# STM32_3_Sheet3.net
KiCad netlist of a schematic drawn in Altium Designer
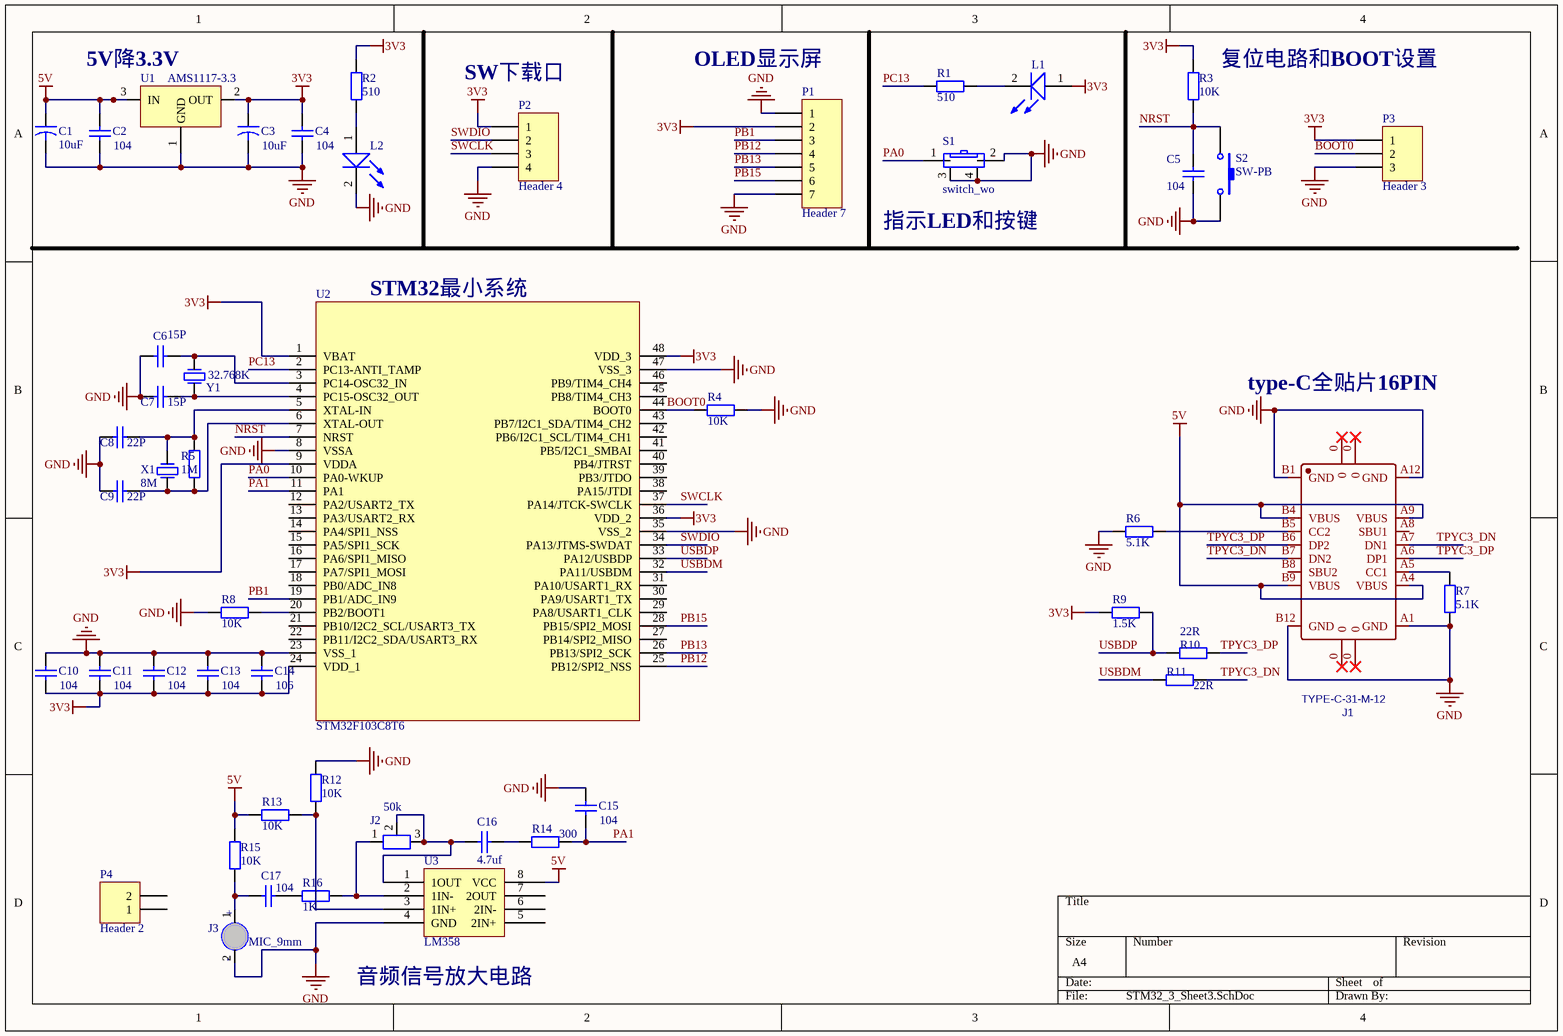
[diagram p0: STM32_3_Sheet3.SchDoc]

(export (version "E")
  (design (tool "Eeschema 10.0.6"))
  (components
    (comp (ref "C1")
      (value "10uF")
      (footprint "RC0805")
      (description "Capacitor")
      (fields (field (name "PUBLISHER") "Altium Limited"))
      (libsource (lib "Miscellaneous Devices") (part "Cap2"))
    )
    (comp (ref "C2")
      (value "104")
      (footprint "RC0603")
      (description "Capacitor")
      (fields (field (name "PUBLISHER") "Altium Limited"))
      (libsource (lib "Miscellaneous Devices") (part "Cap"))
    )
    (comp (ref "C3")
      (value "10uF")
      (footprint "RC0805")
      (description "Capacitor")
      (fields (field (name "PUBLISHER") "Altium Limited"))
      (libsource (lib "Miscellaneous Devices") (part "Cap2"))
    )
    (comp (ref "C4")
      (value "104")
      (footprint "RC0603")
      (description "Capacitor")
      (fields (field (name "PUBLISHER") "Altium Limited"))
      (libsource (lib "Miscellaneous Devices") (part "Cap"))
    )
    (comp (ref "C5")
      (value "104")
      (footprint "RC0603")
      (description "Capacitor")
      (fields (field (name "PUBLISHER") "Altium Limited"))
      (libsource (lib "Miscellaneous Devices") (part "Cap"))
    )
    (comp (ref "C6")
      (value "15P")
      (footprint "RC0603")
      (description "Capacitor")
      (fields (field (name "PUBLISHER") "Altium Limited"))
      (libsource (lib "Miscellaneous Devices") (part "Cap"))
    )
    (comp (ref "C7")
      (value "15P")
      (footprint "RC0603")
      (description "Capacitor")
      (fields (field (name "PUBLISHER") "Altium Limited"))
      (libsource (lib "Miscellaneous Devices") (part "Cap"))
    )
    (comp (ref "C8")
      (value "22P")
      (footprint "RC0603")
      (description "Capacitor")
      (fields (field (name "PUBLISHER") "Altium Limited"))
      (libsource (lib "Miscellaneous Devices") (part "Cap"))
    )
    (comp (ref "C9")
      (value "22P")
      (footprint "RC0603")
      (description "Capacitor")
      (fields (field (name "PUBLISHER") "Altium Limited"))
      (libsource (lib "Miscellaneous Devices") (part "Cap"))
    )
    (comp (ref "C10")
      (value "104")
      (footprint "RC0603")
      (description "Capacitor")
      (fields (field (name "PUBLISHER") "Altium Limited"))
      (libsource (lib "Miscellaneous Devices") (part "Cap"))
    )
    (comp (ref "C11")
      (value "104")
      (footprint "RC0603")
      (description "Capacitor")
      (fields (field (name "PUBLISHER") "Altium Limited"))
      (libsource (lib "Miscellaneous Devices") (part "Cap"))
    )
    (comp (ref "C12")
      (value "104")
      (footprint "RC0603")
      (description "Capacitor")
      (fields (field (name "PUBLISHER") "Altium Limited"))
      (libsource (lib "Miscellaneous Devices") (part "Cap"))
    )
    (comp (ref "C13")
      (value "104")
      (footprint "RC0603")
      (description "Capacitor")
      (fields (field (name "PUBLISHER") "Altium Limited"))
      (libsource (lib "Miscellaneous Devices") (part "Cap"))
    )
    (comp (ref "C14")
      (value "106")
      (footprint "RC0805")
      (description "Capacitor")
      (fields (field (name "PUBLISHER") "Altium Limited"))
      (libsource (lib "Miscellaneous Devices") (part "Cap"))
    )
    (comp (ref "C15")
      (value "104")
      (footprint "RC0603")
      (description "Capacitor")
      (fields (field (name "PUBLISHER") "Altium Limited"))
      (libsource (lib "Miscellaneous Devices") (part "Cap"))
    )
    (comp (ref "C16")
      (value "4.7uf")
      (footprint "RC0805")
      (description "Capacitor")
      (fields (field (name "PUBLISHER") "Altium Limited"))
      (libsource (lib "Miscellaneous Devices") (part "Cap"))
    )
    (comp (ref "C17")
      (value "104")
      (footprint "RC0603")
      (description "Capacitor")
      (fields (field (name "PUBLISHER") "Altium Limited"))
      (libsource (lib "Miscellaneous Devices") (part "Cap"))
    )
    (comp (ref "J1")
      (value "TYPE-C-31-M-12")
      (footprint "USB-TYPE-C_16PIN-MALE-TYPE-C-31-M-12")
      (libsource (lib "STM32_1_Schlib1") (part "TYPE-C-31-M-12"))
    )
    (comp (ref "J2")
      (value "50k")
      (footprint "rv09")
      (description "滑动变阻器")
      (libsource (lib "STM32_1_Schlib1") (part "RES_adjust"))
    )
    (comp (ref "J3")
      (value "MIC_9mm")
      (footprint "MIC9*7MM")
      (description "咪头")
      (libsource (lib "STM32_1_Schlib1") (part "MIC"))
    )
    (comp (ref "L1") (value "1") (footprint "LED0805") (libsource (lib "STM32_1_Schlib1") (part "LED")))
    (comp (ref "L2") (value "1") (footprint "LED0805") (libsource (lib "STM32_1_Schlib1") (part "LED")))
    (comp (ref "P1")
      (value "Header 7")
      (footprint "HDR1X7")
      (description "Header, 7-Pin")
      (fields (field (name "PUBLISHER") "Altium Limited"))
      (libsource (lib "Miscellaneous Connectors") (part "Header 7"))
    )
    (comp (ref "P2")
      (value "Header 4")
      (footprint "HDR1X4")
      (description "Header, 4-Pin")
      (fields (field (name "PUBLISHER") "Altium Limited"))
      (libsource (lib "Miscellaneous Connectors") (part "Header 4"))
    )
    (comp (ref "P3")
      (value "Header 3")
      (footprint "HDR1X3")
      (description "Header, 3-Pin")
      (fields (field (name "PUBLISHER") "Altium Limited"))
      (libsource (lib "Miscellaneous Connectors") (part "Header 3"))
    )
    (comp (ref "P4")
      (value "Header 2")
      (footprint "HDR1X2")
      (description "Header, 2-Pin")
      (fields (field (name "PUBLISHER") "Altium Limited"))
      (libsource (lib "Miscellaneous Connectors") (part "Header 2"))
    )
    (comp (ref "R1")
      (value "510")
      (footprint "RC0603")
      (description "Resistor")
      (fields (field (name "PUBLISHER") "Altium Limited"))
      (libsource (lib "") (part "Res2_2"))
    )
    (comp (ref "R2")
      (value "510")
      (footprint "RC0603")
      (description "Resistor")
      (fields (field (name "PUBLISHER") "Altium Limited"))
      (libsource (lib "Miscellaneous Devices") (part "Res2"))
    )
    (comp (ref "R3")
      (value "10K")
      (footprint "RC0603")
      (description "Resistor")
      (fields (field (name "PUBLISHER") "Altium Limited"))
      (libsource (lib "Miscellaneous Devices") (part "Res2"))
    )
    (comp (ref "R4")
      (value "10K")
      (footprint "RC0603")
      (description "Resistor")
      (fields (field (name "PUBLISHER") "Altium Limited"))
      (libsource (lib "") (part "Res2_1"))
    )
    (comp (ref "R5")
      (value "1M")
      (footprint "RC0603")
      (description "Resistor")
      (fields (field (name "PUBLISHER") "Altium Limited"))
      (libsource (lib "Miscellaneous Devices") (part "Res2"))
    )
    (comp (ref "R6")
      (value "5.1K")
      (footprint "RC0805")
      (description "Resistor")
      (fields (field (name "PUBLISHER") "Altium Limited"))
      (libsource (lib "") (part "Res2_1"))
    )
    (comp (ref "R7")
      (value "5.1K")
      (footprint "RC0805")
      (description "Resistor")
      (fields (field (name "PUBLISHER") "Altium Limited"))
      (libsource (lib "") (part "Res2_3"))
    )
    (comp (ref "R8")
      (value "10K")
      (footprint "RC0603")
      (description "Resistor")
      (fields (field (name "PUBLISHER") "Altium Limited"))
      (libsource (lib "") (part "Res2_1"))
    )
    (comp (ref "R9")
      (value "1.5K")
      (footprint "RC0805")
      (description "Resistor")
      (fields (field (name "PUBLISHER") "Altium Limited"))
      (libsource (lib "") (part "Res2_2"))
    )
    (comp (ref "R10")
      (value "22R")
      (footprint "RC0603")
      (description "Resistor")
      (fields (field (name "PUBLISHER") "Altium Limited"))
      (libsource (lib "") (part "Res2_1"))
    )
    (comp (ref "R11")
      (value "22R")
      (footprint "RC0603")
      (description "Resistor")
      (fields (field (name "PUBLISHER") "Altium Limited"))
      (libsource (lib "") (part "Res2_1"))
    )
    (comp (ref "R12")
      (value "10K")
      (footprint "RC0603")
      (description "Resistor")
      (fields (field (name "PUBLISHER") "Altium Limited"))
      (libsource (lib "Miscellaneous Devices") (part "Res2"))
    )
    (comp (ref "R13")
      (value "10K")
      (footprint "RC0603")
      (description "Resistor")
      (fields (field (name "PUBLISHER") "Altium Limited"))
      (libsource (lib "") (part "Res2_1"))
    )
    (comp (ref "R14")
      (value "300")
      (footprint "RC0805")
      (description "Resistor")
      (fields (field (name "PUBLISHER") "Altium Limited"))
      (libsource (lib "") (part "Res2_2"))
    )
    (comp (ref "R15")
      (value "10K")
      (footprint "RC0603")
      (description "Resistor")
      (fields (field (name "PUBLISHER") "Altium Limited"))
      (libsource (lib "") (part "Res2_3"))
    )
    (comp (ref "R16")
      (value "1K")
      (footprint "RC0805")
      (description "Resistor")
      (fields (field (name "PUBLISHER") "Altium Limited"))
      (libsource (lib "") (part "Res2_2"))
    )
    (comp (ref "S1")
      (value "switch_wo")
      (footprint "TSW DIP-3*6*5_V")
      (description "卧式开关")
      (libsource (lib "STM32_1_Schlib1") (part "switch_wo"))
    )
    (comp (ref "S2")
      (value "SW-PB")
      (footprint "SMT-KEY")
      (description "Switch")
      (fields (field (name "PUBLISHER") "Altium Limited"))
      (libsource (lib "Miscellaneous Devices") (part "SW-PB"))
    )
    (comp (ref "U1")
      (value "AMS1117-3.3")
      (footprint "SOT89_M")
      (description "5V稳3.3V")
      (libsource (lib "STM32_1_Schlib1") (part "AMS1117-3.3"))
    )
    (comp (ref "U2")
      (value "STM32F103C8T6")
      (footprint "LQFP48")
      (description "STM32")
      (libsource (lib "altium-import") (part "root_0_STM32F103C8T6_"))
    )
    (comp (ref "U3")
      (value "LM358")
      (footprint "SOP8_M")
      (description "音频放大")
      (libsource (lib "STM32_1_Schlib1") (part "LM358"))
    )
    (comp (ref "X1")
      (value "8M")
      (footprint "OSC 5032-2P")
      (description "晶振")
      (libsource (lib "STM32_1_Schlib1") (part "Y1"))
    )
    (comp (ref "Y1")
      (value "32.768K")
      (footprint "OSC 3215-2P")
      (description "晶振")
      (libsource (lib "STM32_1_Schlib1") (part "Y1"))
    )
  )
  (nets
    (net (code "1") (name "/BOOT0") (class "Default")
      (node (ref "P3") (pin "2") (pinfunction "2_2") (pintype "passive"))
      (node (ref "R4") (pin "2") (pinfunction "2_2") (pintype "passive"))
      (node (ref "U2") (pin "44") (pinfunction "BOOT0_44") (pintype "passive"))
    )
    (net (code "2") (name "/NRST") (class "Default")
      (node (ref "C5") (pin "1") (pinfunction "1_1") (pintype "passive"))
      (node (ref "R3") (pin "1") (pinfunction "1_1") (pintype "passive"))
      (node (ref "S2") (pin "1") (pinfunction "1_1") (pintype "passive"))
      (node (ref "U2") (pin "7") (pinfunction "NRST_7") (pintype "passive"))
    )
    (net (code "3") (name "/PA0") (class "Default")
      (node (ref "S1") (pin "1") (pinfunction "1_1") (pintype "passive"))
      (node (ref "U2") (pin "10") (pinfunction "PA0-WKUP_10") (pintype "passive"))
    )
    (net (code "4") (name "/PA1") (class "Default")
      (node (ref "C15") (pin "1") (pinfunction "1_1") (pintype "passive"))
      (node (ref "R14") (pin "2") (pinfunction "2_2") (pintype "passive"))
      (node (ref "U2") (pin "11") (pinfunction "PA1_11") (pintype "passive"))
    )
    (net (code "5") (name "/PB1") (class "Default")
      (node (ref "P1") (pin "3") (pinfunction "3_3") (pintype "passive"))
      (node (ref "U2") (pin "19") (pinfunction "PB1/ADC_IN9_19") (pintype "passive"))
    )
    (net (code "6") (name "/PB12") (class "Default")
      (node (ref "P1") (pin "4") (pinfunction "4_4") (pintype "passive"))
      (node (ref "U2") (pin "25") (pinfunction "PB12/SPI2_NSS_25") (pintype "passive"))
    )
    (net (code "7") (name "/PB13") (class "Default")
      (node (ref "P1") (pin "5") (pinfunction "5_5") (pintype "passive"))
      (node (ref "U2") (pin "26") (pinfunction "PB13/SPI2_SCK_26") (pintype "passive"))
    )
    (net (code "8") (name "/PB15") (class "Default")
      (node (ref "P1") (pin "6") (pinfunction "6_6") (pintype "passive"))
      (node (ref "U2") (pin "28") (pinfunction "PB15/SPI2_MOSI_28") (pintype "passive"))
    )
    (net (code "9") (name "/PC13") (class "Default")
      (node (ref "R1") (pin "1") (pinfunction "1_1") (pintype "passive"))
      (node (ref "U2") (pin "2") (pinfunction "PC13-ANTI_TAMP_2") (pintype "passive"))
    )
    (net (code "10") (name "/SWCLK") (class "Default")
      (node (ref "P2") (pin "3") (pinfunction "3_3") (pintype "passive"))
      (node (ref "U2") (pin "37") (pinfunction "PA14/JTCK-SWCLK_37") (pintype "passive"))
    )
    (net (code "11") (name "/SWDIO") (class "Default")
      (node (ref "P2") (pin "2") (pinfunction "2_2") (pintype "passive"))
      (node (ref "U2") (pin "34") (pinfunction "PA13/JTMS-SWDAT_34") (pintype "passive"))
    )
    (net (code "12") (name "/TPYC3_DN") (class "Default")
      (node (ref "J1") (pin "A7") (pinfunction "DN1_A7") (pintype "passive"))
      (node (ref "J1") (pin "B7") (pinfunction "DN2_B7") (pintype "passive"))
      (node (ref "R11") (pin "1") (pinfunction "1_1") (pintype "passive"))
    )
    (net (code "13") (name "/TPYC3_DP") (class "Default")
      (node (ref "J1") (pin "A6") (pinfunction "DP1_A6") (pintype "passive"))
      (node (ref "J1") (pin "B6") (pinfunction "DP2_B6") (pintype "passive"))
      (node (ref "R10") (pin "1") (pinfunction "1_1") (pintype "passive"))
    )
    (net (code "14") (name "/USBDM") (class "Default")
      (node (ref "R11") (pin "2") (pinfunction "2_2") (pintype "passive"))
      (node (ref "U2") (pin "32") (pinfunction "PA11/USBDM_32") (pintype "passive"))
    )
    (net (code "15") (name "/USBDP") (class "Default")
      (node (ref "R10") (pin "2") (pinfunction "2_2") (pintype "passive"))
      (node (ref "R9") (pin "2") (pinfunction "2_2") (pintype "passive"))
      (node (ref "U2") (pin "33") (pinfunction "PA12/USBDP_33") (pintype "passive"))
    )
    (net (code "16") (name "3V3") (class "Default")
      (node (ref "C10") (pin "1") (pinfunction "1_1") (pintype "passive"))
      (node (ref "C11") (pin "1") (pinfunction "1_1") (pintype "passive"))
      (node (ref "C12") (pin "1") (pinfunction "1_1") (pintype "passive"))
      (node (ref "C13") (pin "1") (pinfunction "1_1") (pintype "passive"))
      (node (ref "C14") (pin "1") (pinfunction "1_1") (pintype "passive"))
      (node (ref "C3") (pin "1") (pinfunction "1_1") (pintype "passive"))
      (node (ref "C4") (pin "2") (pinfunction "2_2") (pintype "passive"))
      (node (ref "L1") (pin "1") (pinfunction "1_1") (pintype "passive"))
      (node (ref "P1") (pin "2") (pinfunction "2_2") (pintype "passive"))
      (node (ref "P2") (pin "1") (pinfunction "1_1") (pintype "passive"))
      (node (ref "P3") (pin "1") (pinfunction "1_1") (pintype "passive"))
      (node (ref "R2") (pin "2") (pinfunction "2_2") (pintype "passive"))
      (node (ref "R3") (pin "2") (pinfunction "2_2") (pintype "passive"))
      (node (ref "R9") (pin "1") (pinfunction "1_1") (pintype "passive"))
      (node (ref "U1") (pin "2") (pinfunction "OUT_2") (pintype "passive"))
      (node (ref "U2") (pin "1") (pinfunction "VBAT_1") (pintype "passive"))
      (node (ref "U2") (pin "24") (pinfunction "VDD_1_24") (pintype "passive"))
      (node (ref "U2") (pin "36") (pinfunction "VDD_2_36") (pintype "passive"))
      (node (ref "U2") (pin "48") (pinfunction "VDD_3_48") (pintype "passive"))
      (node (ref "U2") (pin "9") (pinfunction "VDDA_9") (pintype "passive"))
    )
    (net (code "17") (name "5V") (class "Default")
      (node (ref "C1") (pin "1") (pinfunction "1_1") (pintype "passive"))
      (node (ref "C2") (pin "2") (pinfunction "2_2") (pintype "passive"))
      (node (ref "J1") (pin "A4") (pinfunction "VBUS_A4") (pintype "passive"))
      (node (ref "J1") (pin "A9") (pinfunction "VBUS_A9") (pintype "passive"))
      (node (ref "J1") (pin "B4") (pinfunction "VBUS_B4") (pintype "passive"))
      (node (ref "J1") (pin "B9") (pinfunction "VBUS_B9") (pintype "passive"))
      (node (ref "R13") (pin "2") (pinfunction "2_2") (pintype "passive"))
      (node (ref "R15") (pin "1") (pinfunction "1_1") (pintype "passive"))
      (node (ref "U1") (pin "3") (pinfunction "IN_3") (pintype "passive"))
      (node (ref "U3") (pin "8") (pinfunction "VCC_8") (pintype "passive"))
    )
    (net (code "18") (name "GND") (class "Default")
      (node (ref "C1") (pin "2") (pinfunction "2_2") (pintype "passive"))
      (node (ref "C10") (pin "2") (pinfunction "2_2") (pintype "passive"))
      (node (ref "C11") (pin "2") (pinfunction "2_2") (pintype "passive"))
      (node (ref "C12") (pin "2") (pinfunction "2_2") (pintype "passive"))
      (node (ref "C13") (pin "2") (pinfunction "2_2") (pintype "passive"))
      (node (ref "C14") (pin "2") (pinfunction "2_2") (pintype "passive"))
      (node (ref "C15") (pin "2") (pinfunction "2_2") (pintype "passive"))
      (node (ref "C2") (pin "1") (pinfunction "1_1") (pintype "passive"))
      (node (ref "C3") (pin "2") (pinfunction "2_2") (pintype "passive"))
      (node (ref "C4") (pin "1") (pinfunction "1_1") (pintype "passive"))
      (node (ref "C5") (pin "2") (pinfunction "2_2") (pintype "passive"))
      (node (ref "C6") (pin "1") (pinfunction "1_1") (pintype "passive"))
      (node (ref "C7") (pin "2") (pinfunction "2_2") (pintype "passive"))
      (node (ref "C8") (pin "2") (pinfunction "2_2") (pintype "passive"))
      (node (ref "C9") (pin "2") (pinfunction "2_2") (pintype "passive"))
      (node (ref "J1") (pin "A1") (pinfunction "GND_A1") (pintype "passive"))
      (node (ref "J1") (pin "A12") (pinfunction "GND_A12") (pintype "passive"))
      (node (ref "J1") (pin "B1") (pinfunction "GND_B1") (pintype "passive"))
      (node (ref "J1") (pin "B12") (pinfunction "GND_B12") (pintype "passive"))
      (node (ref "J3") (pin "2") (pinfunction "2_2") (pintype "passive"))
      (node (ref "L2") (pin "2") (pinfunction "2_2") (pintype "passive"))
      (node (ref "P1") (pin "1") (pinfunction "1_1") (pintype "passive"))
      (node (ref "P1") (pin "7") (pinfunction "7_7") (pintype "passive"))
      (node (ref "P2") (pin "4") (pinfunction "4_4") (pintype "passive"))
      (node (ref "P3") (pin "3") (pinfunction "3_3") (pintype "passive"))
      (node (ref "R12") (pin "2") (pinfunction "2_2") (pintype "passive"))
      (node (ref "R4") (pin "1") (pinfunction "1_1") (pintype "passive"))
      (node (ref "R6") (pin "2") (pinfunction "2_2") (pintype "passive"))
      (node (ref "R7") (pin "2") (pinfunction "2_2") (pintype "passive"))
      (node (ref "R8") (pin "2") (pinfunction "2_2") (pintype "passive"))
      (node (ref "S1") (pin "2") (pinfunction "2_2") (pintype "passive"))
      (node (ref "S1") (pin "3") (pinfunction "3_3") (pintype "passive"))
      (node (ref "S1") (pin "4") (pinfunction "4_4") (pintype "passive"))
      (node (ref "S2") (pin "2") (pinfunction "2_2") (pintype "passive"))
      (node (ref "U1") (pin "1") (pinfunction "GND_1") (pintype "passive"))
      (node (ref "U2") (pin "23") (pinfunction "VSS_1_23") (pintype "passive"))
      (node (ref "U2") (pin "35") (pinfunction "VSS_2_35") (pintype "passive"))
      (node (ref "U2") (pin "47") (pinfunction "VSS_3_47") (pintype "passive"))
      (node (ref "U2") (pin "8") (pinfunction "VSSA_8") (pintype "passive"))
      (node (ref "U3") (pin "4") (pinfunction "GND_4") (pintype "passive"))
    )
    (net (code "19") (name "Net-(C16-Pad1)") (class "Default")
      (node (ref "C16") (pin "1") (pinfunction "1_1") (pintype "passive"))
      (node (ref "R14") (pin "1") (pinfunction "1_1") (pintype "passive"))
    )
    (net (code "20") (name "Net-(C17-Pad1)") (class "Default")
      (node (ref "C17") (pin "1") (pinfunction "1_1") (pintype "passive"))
      (node (ref "R16") (pin "1") (pinfunction "1_1") (pintype "passive"))
    )
    (net (code "21") (name "Net-(C17-Pad2)") (class "Default")
      (node (ref "C17") (pin "2") (pinfunction "2_2") (pintype "passive"))
      (node (ref "J3") (pin "1") (pinfunction "1_1") (pintype "passive"))
      (node (ref "R15") (pin "2") (pinfunction "2_2") (pintype "passive"))
    )
    (net (code "22") (name "Net-(J1-CC1)") (class "Default")
      (node (ref "J1") (pin "A5") (pinfunction "CC1_A5") (pintype "passive"))
      (node (ref "R7") (pin "1") (pinfunction "1_1") (pintype "passive"))
    )
    (net (code "23") (name "Net-(J1-CC2)") (class "Default")
      (node (ref "J1") (pin "B5") (pinfunction "CC2_B5") (pintype "passive"))
      (node (ref "R6") (pin "1") (pinfunction "1_1") (pintype "passive"))
    )
    (net (code "24") (name "Net-(L1-Pad2)") (class "Default")
      (node (ref "L1") (pin "2") (pinfunction "2_2") (pintype "passive"))
      (node (ref "R1") (pin "2") (pinfunction "2_2") (pintype "passive"))
    )
    (net (code "25") (name "Net-(L2-Pad1)") (class "Default")
      (node (ref "L2") (pin "1") (pinfunction "1_1") (pintype "passive"))
      (node (ref "R2") (pin "1") (pinfunction "1_1") (pintype "passive"))
    )
    (net (code "26") (name "Net-(U2-PB2{slash}BOOT1)") (class "Default")
      (node (ref "R8") (pin "1") (pinfunction "1_1") (pintype "passive"))
      (node (ref "U2") (pin "20") (pinfunction "PB2/BOOT1_20") (pintype "passive"))
    )
    (net (code "27") (name "Net-(U2-PC14-OSC32_IN)") (class "Default")
      (node (ref "C6") (pin "2") (pinfunction "2_2") (pintype "passive"))
      (node (ref "U2") (pin "3") (pinfunction "PC14-OSC32_IN_3") (pintype "passive"))
      (node (ref "Y1") (pin "1") (pinfunction "1_1") (pintype "passive"))
    )
    (net (code "28") (name "Net-(U2-PC15-OSC32_OUT)") (class "Default")
      (node (ref "C7") (pin "1") (pinfunction "1_1") (pintype "passive"))
      (node (ref "U2") (pin "4") (pinfunction "PC15-OSC32_OUT_4") (pintype "passive"))
      (node (ref "Y1") (pin "2") (pinfunction "2_2") (pintype "passive"))
    )
    (net (code "29") (name "Net-(U2-XTAL-IN)") (class "Default")
      (node (ref "C8") (pin "1") (pinfunction "1_1") (pintype "passive"))
      (node (ref "R5") (pin "2") (pinfunction "2_2") (pintype "passive"))
      (node (ref "U2") (pin "5") (pinfunction "XTAL-IN_5") (pintype "passive"))
      (node (ref "X1") (pin "1") (pinfunction "1_1") (pintype "passive"))
    )
    (net (code "30") (name "Net-(U2-XTAL-OUT)") (class "Default")
      (node (ref "C9") (pin "1") (pinfunction "1_1") (pintype "passive"))
      (node (ref "R5") (pin "1") (pinfunction "1_1") (pintype "passive"))
      (node (ref "U2") (pin "6") (pinfunction "XTAL-OUT_6") (pintype "passive"))
      (node (ref "X1") (pin "2") (pinfunction "2_2") (pintype "passive"))
    )
    (net (code "31") (name "Net-(U3-1IN+)") (class "Default")
      (node (ref "R12") (pin "1") (pinfunction "1_1") (pintype "passive"))
      (node (ref "R13") (pin "1") (pinfunction "1_1") (pintype "passive"))
      (node (ref "U3") (pin "3") (pinfunction "1IN+_3") (pintype "passive"))
    )
    (net (code "32") (name "Net-(U3-1IN-)") (class "Default")
      (node (ref "J2") (pin "1") (pinfunction "1_1") (pintype "passive"))
      (node (ref "R16") (pin "2") (pinfunction "2_2") (pintype "passive"))
      (node (ref "U3") (pin "2") (pinfunction "1IN-_2") (pintype "passive"))
    )
    (net (code "33") (name "Net-(U3-1OUT)") (class "Default")
      (node (ref "C16") (pin "2") (pinfunction "2_2") (pintype "passive"))
      (node (ref "J2") (pin "2") (pinfunction "2_2") (pintype "passive"))
      (node (ref "J2") (pin "3") (pinfunction "3_3") (pintype "passive"))
      (node (ref "U3") (pin "1") (pinfunction "1OUT_1") (pintype "passive"))
    )
    (net (code "34") (name "unconnected-(J1-Pad0)") (class "Default")
      (node (ref "J1") (pin "0") (pinfunction "0_0") (pintype "passive+no_connect"))
    )
    (net (code "35") (name "unconnected-(J1-Pad0)_1") (class "Default")
      (node (ref "J1") (pin "0") (pinfunction "0_0") (pintype "passive+no_connect"))
    )
    (net (code "36") (name "unconnected-(J1-Pad0)_2") (class "Default")
      (node (ref "J1") (pin "0") (pinfunction "0_0") (pintype "passive+no_connect"))
    )
    (net (code "37") (name "unconnected-(J1-Pad0)_3") (class "Default")
      (node (ref "J1") (pin "0") (pinfunction "0_0") (pintype "passive+no_connect"))
    )
    (net (code "38") (name "unconnected-(J1-SBU1-PadA8)") (class "Default")
      (node (ref "J1") (pin "A8") (pinfunction "SBU1_A8") (pintype "passive"))
    )
    (net (code "39") (name "unconnected-(J1-SBU2-PadB8)") (class "Default")
      (node (ref "J1") (pin "B8") (pinfunction "SBU2_B8") (pintype "passive"))
    )
    (net (code "40") (name "unconnected-(P4-Pad1)") (class "Default")
      (node (ref "P4") (pin "1") (pinfunction "1_1") (pintype "passive"))
    )
    (net (code "41") (name "unconnected-(P4-Pad2)") (class "Default")
      (node (ref "P4") (pin "2") (pinfunction "2_2") (pintype "passive"))
    )
    (net (code "42") (name "unconnected-(U2-PA2{slash}USART2_TX-Pad12)") (class "Default")
      (node (ref "U2") (pin "12") (pinfunction "PA2/USART2_TX_12") (pintype "passive"))
    )
    (net (code "43") (name "unconnected-(U2-PA3{slash}USART2_RX-Pad13)") (class "Default")
      (node (ref "U2") (pin "13") (pinfunction "PA3/USART2_RX_13") (pintype "passive"))
    )
    (net (code "44") (name "unconnected-(U2-PA4{slash}SPI1_NSS-Pad14)") (class "Default")
      (node (ref "U2") (pin "14") (pinfunction "PA4/SPI1_NSS_14") (pintype "passive"))
    )
    (net (code "45") (name "unconnected-(U2-PA5{slash}SPI1_SCK-Pad15)") (class "Default")
      (node (ref "U2") (pin "15") (pinfunction "PA5/SPI1_SCK_15") (pintype "passive"))
    )
    (net (code "46") (name "unconnected-(U2-PA6{slash}SPI1_MISO-Pad16)") (class "Default")
      (node (ref "U2") (pin "16") (pinfunction "PA6/SPI1_MISO_16") (pintype "passive"))
    )
    (net (code "47") (name "unconnected-(U2-PA7{slash}SPI1_MOSI-Pad17)") (class "Default")
      (node (ref "U2") (pin "17") (pinfunction "PA7/SPI1_MOSI_17") (pintype "passive"))
    )
    (net (code "48") (name "unconnected-(U2-PA8{slash}USART1_CLK-Pad29)") (class "Default")
      (node (ref "U2") (pin "29") (pinfunction "PA8/USART1_CLK_29") (pintype "passive"))
    )
    (net (code "49") (name "unconnected-(U2-PA9{slash}USART1_TX-Pad30)") (class "Default")
      (node (ref "U2") (pin "30") (pinfunction "PA9/USART1_TX_30") (pintype "passive"))
    )
    (net (code "50") (name "unconnected-(U2-PA10{slash}USART1_RX-Pad31)") (class "Default")
      (node (ref "U2") (pin "31") (pinfunction "PA10/USART1_RX_31") (pintype "passive"))
    )
    (net (code "51") (name "unconnected-(U2-PA15{slash}JTDI-Pad38)") (class "Default")
      (node (ref "U2") (pin "38") (pinfunction "PA15/JTDI_38") (pintype "passive"))
    )
    (net (code "52") (name "unconnected-(U2-PB0{slash}ADC_IN8-Pad18)") (class "Default")
      (node (ref "U2") (pin "18") (pinfunction "PB0/ADC_IN8_18") (pintype "passive"))
    )
    (net (code "53") (name "unconnected-(U2-PB3{slash}JTDO-Pad39)") (class "Default")
      (node (ref "U2") (pin "39") (pinfunction "PB3/JTDO_39") (pintype "passive"))
    )
    (net (code "54") (name "unconnected-(U2-PB4{slash}JTRST-Pad40)") (class "Default")
      (node (ref "U2") (pin "40") (pinfunction "PB4/JTRST_40") (pintype "passive"))
    )
    (net (code "55") (name "unconnected-(U2-PB5{slash}I2C1_SMBAI-Pad41)") (class "Default")
      (node (ref "U2") (pin "41") (pinfunction "PB5/I2C1_SMBAI_41") (pintype "passive"))
    )
    (net (code "56") (name "unconnected-(U2-PB6{slash}I2C1_SCL{slash}TIM4_CH1-Pad42)") (class "Default")
      (node (ref "U2") (pin "42") (pinfunction "PB6/I2C1_SCL/TIM4_CH1_42") (pintype "passive"))
    )
    (net (code "57") (name "unconnected-(U2-PB7{slash}I2C1_SDA{slash}TIM4_CH2-Pad43)") (class "Default")
      (node (ref "U2") (pin "43") (pinfunction "PB7/I2C1_SDA/TIM4_CH2_43") (pintype "passive"))
    )
    (net (code "58") (name "unconnected-(U2-PB8{slash}TIM4_CH3-Pad45)") (class "Default")
      (node (ref "U2") (pin "45") (pinfunction "PB8/TIM4_CH3_45") (pintype "passive"))
    )
    (net (code "59") (name "unconnected-(U2-PB9{slash}TIM4_CH4-Pad46)") (class "Default")
      (node (ref "U2") (pin "46") (pinfunction "PB9/TIM4_CH4_46") (pintype "passive"))
    )
    (net (code "60") (name "unconnected-(U2-PB10{slash}I2C2_SCL{slash}USART3_TX-Pad21)") (class "Default")
      (node (ref "U2") (pin "21") (pinfunction "PB10/I2C2_SCL/USART3_TX_21") (pintype "passive"))
    )
    (net (code "61") (name "unconnected-(U2-PB11{slash}I2C2_SDA{slash}USART3_RX-Pad22)") (class "Default")
      (node (ref "U2") (pin "22") (pinfunction "PB11/I2C2_SDA/USART3_RX_22") (pintype "passive"))
    )
    (net (code "62") (name "unconnected-(U2-PB14{slash}SPI2_MISO-Pad27)") (class "Default")
      (node (ref "U2") (pin "27") (pinfunction "PB14/SPI2_MISO_27") (pintype "passive"))
    )
    (net (code "63") (name "unconnected-(U3-2IN+-Pad5)") (class "Default")
      (node (ref "U3") (pin "5") (pinfunction "2IN+_5") (pintype "passive"))
    )
    (net (code "64") (name "unconnected-(U3-2IN--Pad6)") (class "Default")
      (node (ref "U3") (pin "6") (pinfunction "2IN-_6") (pintype "passive"))
    )
    (net (code "65") (name "unconnected-(U3-2OUT-Pad7)") (class "Default")
      (node (ref "U3") (pin "7") (pinfunction "2OUT_7") (pintype "passive"))
    )
  )
)
